# CasTracker.net
KiCad netlist of a schematic drawn in EAGLE
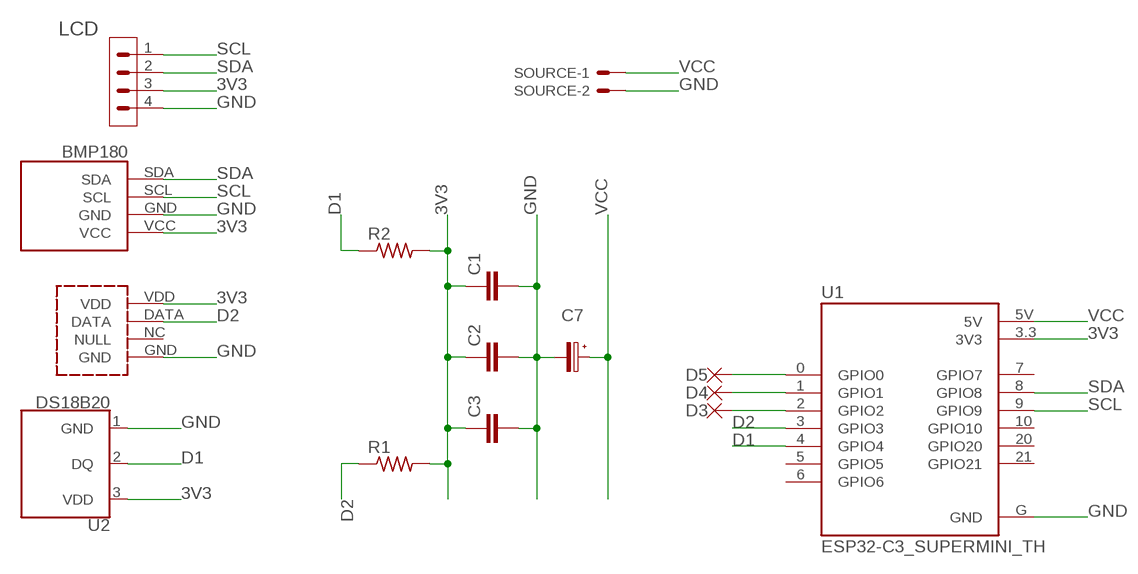
[diagram p0: schematic, sheet 1]

(export (version "E")
  (design (tool "Eeschema 10.0.6"))
  (components
    (comp (ref "BMP180")
      (value "GY-68-BMP180")
      (footprint "eagle-import:GY-68-BMP180")
      (libsource (lib "eagle-import") (part "GY-68-BMP180"))
    )
    (comp (ref "C1")
      (value "C2.5/2")
      (footprint "eagle-import:C2.5-2")
      (libsource (lib "eagle-import") (part "C2.5/2"))
    )
    (comp (ref "C2")
      (value "C2.5/2")
      (footprint "eagle-import:C2.5-2")
      (libsource (lib "eagle-import") (part "C2.5/2"))
    )
    (comp (ref "C3")
      (value "C2.5/2")
      (footprint "eagle-import:C2.5-2")
      (libsource (lib "eagle-import") (part "C2.5/2"))
    )
    (comp (ref "C7")
      (value "100u")
      (footprint "eagle-import:CAPPRD508W65D1000H1100B")
      (libsource (lib "eagle-import") (part "C-POLRADIAL-11MM-DIA_"))
    )
    (comp (ref "D3")
      (value "PAD")
      (footprint "eagle-import:2.54_1.0")
      (libsource (lib "eagle-import") (part "PAD"))
    )
    (comp (ref "D4")
      (value "PAD")
      (footprint "eagle-import:2.54_1.0")
      (libsource (lib "eagle-import") (part "PAD"))
    )
    (comp (ref "D5")
      (value "PAD")
      (footprint "eagle-import:2.54_1.0")
      (libsource (lib "eagle-import") (part "PAD"))
    )
    (comp (ref "DHT22")
      (value "DHT22")
      (footprint "eagle-import:DHT22")
      (fields (field (name "MF") "Aosong Electronics"))
      (libsource (lib "eagle-import") (part "DHT22"))
    )
    (comp (ref "LCD")
      (value "PINHD-1X4/90")
      (footprint "eagle-import:1X04_90")
      (libsource (lib "eagle-import") (part "PINHD-1X4/90"))
    )
    (comp (ref "R1")
      (value "R-US_0204/2V")
      (footprint "eagle-import:0204V")
      (libsource (lib "eagle-import") (part "R-US_0204/2V"))
    )
    (comp (ref "R2")
      (value "R-US_0204/2V")
      (footprint "eagle-import:0204V")
      (libsource (lib "eagle-import") (part "R-US_0204/2V"))
    )
    (comp (ref "SOURCE")
      (value "CON-MOLEX_22-23-2021")
      (footprint "eagle-import:CON-MOLEX_22-23-2021")
      (fields (field (name "MF") "Molex") (field (name "MP") "22-23-2021"))
      (libsource (lib "eagle-import") (part "CON-MOLEX_22-23-2021"))
    )
    (comp (ref "U1")
      (value "ESP32-C3_SUPERMINI_TH")
      (footprint "eagle-import:MODULE_ESP32-C3_SUPERMINI_TH")
      (fields (field (name "MF") "Espressif Systems") (field (name "MP") "ESP32-C3 SuperMini_TH"))
      (libsource (lib "eagle-import") (part "ESP32-C3_SUPERMINI_TH"))
    )
    (comp (ref "U2")
      (value "DS18B20")
      (footprint "eagle-import:TO-92-AMMO")
      (libsource (lib "eagle-import") (part "DS18B20"))
    )
  )
  (nets
    (net (code "1") (name "/3V3") (class "Default")
      (node (ref "BMP180") (pin "VCC") (pinfunction "VCC_VCC") (pintype "bidirectional"))
      (node (ref "C1") (pin "1") (pinfunction "1_1") (pintype "passive"))
      (node (ref "C2") (pin "1") (pinfunction "1_1") (pintype "passive"))
      (node (ref "C3") (pin "1") (pinfunction "1_1") (pintype "passive"))
      (node (ref "DHT22") (pin "VDD") (pinfunction "VDD_VDD") (pintype "power_in"))
      (node (ref "LCD") (pin "3") (pinfunction "3_3") (pintype "passive"))
      (node (ref "R1") (pin "2") (pinfunction "2_2") (pintype "passive"))
      (node (ref "R2") (pin "2") (pinfunction "2_2") (pintype "passive"))
      (node (ref "U1") (pin "3.3") (pinfunction "3V3_3.3") (pintype "power_in"))
      (node (ref "U2") (pin "3") (pinfunction "VDD_3") (pintype "power_in"))
    )
    (net (code "2") (name "/D1") (class "Default")
      (node (ref "R2") (pin "1") (pinfunction "1_1") (pintype "passive"))
      (node (ref "U1") (pin "4") (pinfunction "GPIO4_4") (pintype "bidirectional"))
      (node (ref "U2") (pin "2") (pinfunction "DQ_2") (pintype "bidirectional"))
    )
    (net (code "3") (name "/D2") (class "Default")
      (node (ref "DHT22") (pin "DATA") (pinfunction "DATA_DATA") (pintype "output"))
      (node (ref "R1") (pin "1") (pinfunction "1_1") (pintype "passive"))
      (node (ref "U1") (pin "3") (pinfunction "GPIO3_3") (pintype "bidirectional"))
    )
    (net (code "4") (name "/GND") (class "Default")
      (node (ref "BMP180") (pin "GND") (pinfunction "GND_GND") (pintype "bidirectional"))
      (node (ref "C1") (pin "2") (pinfunction "2_2") (pintype "passive"))
      (node (ref "C2") (pin "2") (pinfunction "2_2") (pintype "passive"))
      (node (ref "C3") (pin "2") (pinfunction "2_2") (pintype "passive"))
      (node (ref "C7") (pin "2") (pinfunction "-_2") (pintype "passive"))
      (node (ref "DHT22") (pin "GND") (pinfunction "GND_GND") (pintype "power_in"))
      (node (ref "LCD") (pin "4") (pinfunction "4_4") (pintype "passive"))
      (node (ref "SOURCE") (pin "2") (pinfunction "S_2") (pintype "passive"))
      (node (ref "U1") (pin "G") (pinfunction "GND_G") (pintype "power_in"))
      (node (ref "U2") (pin "1") (pinfunction "GND_1") (pintype "power_in"))
    )
    (net (code "5") (name "/SCL") (class "Default")
      (node (ref "BMP180") (pin "SCL") (pinfunction "SCL_SCL") (pintype "bidirectional"))
      (node (ref "LCD") (pin "1") (pinfunction "1_1") (pintype "passive"))
      (node (ref "U1") (pin "9") (pinfunction "GPIO9_9") (pintype "bidirectional"))
    )
    (net (code "6") (name "/SDA") (class "Default")
      (node (ref "BMP180") (pin "SDA") (pinfunction "SDA_SDA") (pintype "bidirectional"))
      (node (ref "LCD") (pin "2") (pinfunction "2_2") (pintype "passive"))
      (node (ref "U1") (pin "8") (pinfunction "GPIO8_8") (pintype "bidirectional"))
    )
    (net (code "7") (name "/VCC") (class "Default")
      (node (ref "C7") (pin "1") (pinfunction "+_1") (pintype "passive"))
      (node (ref "SOURCE") (pin "1") (pinfunction "S_1") (pintype "passive"))
      (node (ref "U1") (pin "5V") (pinfunction "5V_5V") (pintype "power_in"))
    )
    (net (code "8") (name "Net-(D3-P)") (class "Default")
      (node (ref "D3") (pin "1") (pinfunction "P_1") (pintype "passive"))
      (node (ref "U1") (pin "2") (pinfunction "GPIO2_2") (pintype "bidirectional"))
    )
    (net (code "9") (name "Net-(D4-P)") (class "Default")
      (node (ref "D4") (pin "1") (pinfunction "P_1") (pintype "passive"))
      (node (ref "U1") (pin "1") (pinfunction "GPIO1_1") (pintype "bidirectional"))
    )
    (net (code "10") (name "Net-(D5-P)") (class "Default")
      (node (ref "D5") (pin "1") (pinfunction "P_1") (pintype "passive"))
      (node (ref "U1") (pin "0") (pinfunction "GPIO0_0") (pintype "bidirectional"))
    )
    (net (code "11") (name "unconnected-(DHT22-NULL-PadNC)") (class "Default")
      (node (ref "DHT22") (pin "NC") (pinfunction "NULL_NC") (pintype "no_connect"))
    )
    (net (code "12") (name "unconnected-(U1-GPIO5-Pad5)") (class "Default")
      (node (ref "U1") (pin "5") (pinfunction "GPIO5_5") (pintype "bidirectional"))
    )
    (net (code "13") (name "unconnected-(U1-GPIO6-Pad6)") (class "Default")
      (node (ref "U1") (pin "6") (pinfunction "GPIO6_6") (pintype "bidirectional"))
    )
    (net (code "14") (name "unconnected-(U1-GPIO7-Pad7)") (class "Default")
      (node (ref "U1") (pin "7") (pinfunction "GPIO7_7") (pintype "bidirectional"))
    )
    (net (code "15") (name "unconnected-(U1-GPIO10-Pad10)") (class "Default")
      (node (ref "U1") (pin "10") (pinfunction "GPIO10_10") (pintype "bidirectional"))
    )
    (net (code "16") (name "unconnected-(U1-GPIO20-Pad20)") (class "Default")
      (node (ref "U1") (pin "20") (pinfunction "GPIO20_20") (pintype "bidirectional"))
    )
    (net (code "17") (name "unconnected-(U1-GPIO21-Pad21)") (class "Default")
      (node (ref "U1") (pin "21") (pinfunction "GPIO21_21") (pintype "bidirectional"))
    )
  )
)
